# flbmain.net
KiCad netlist of a schematic drawn in Altium Designer
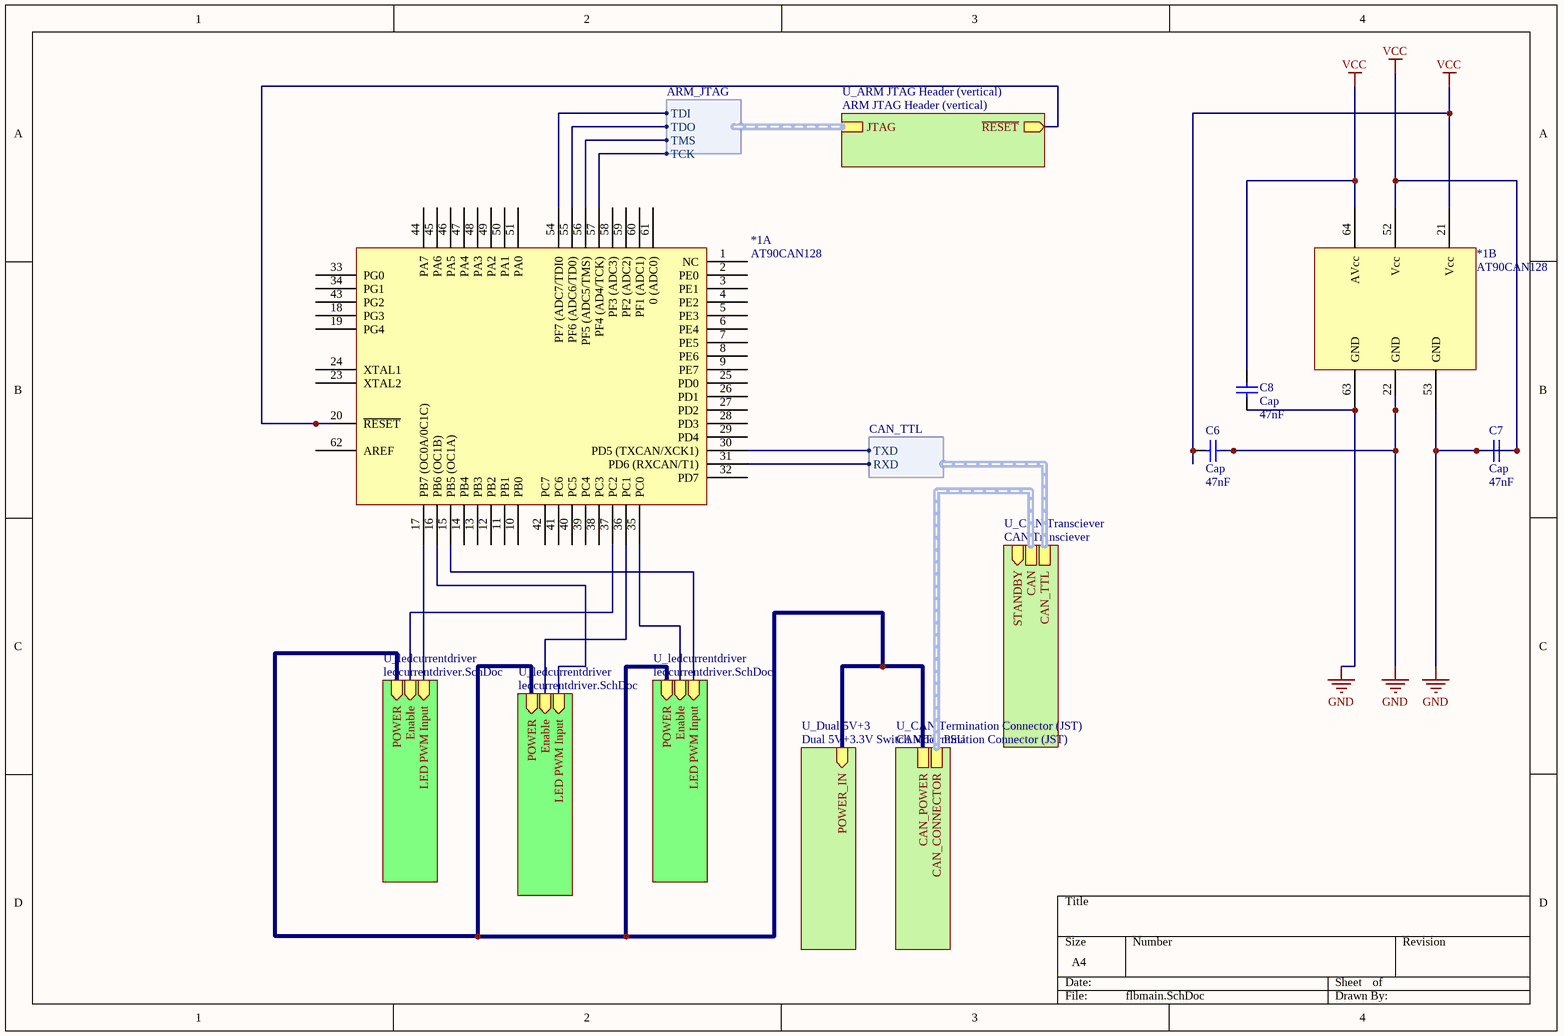
[diagram p0: flbmain.SchDoc]

(export (version "E")
  (design (tool "Eeschema 10.0.6"))
  (components
    (comp (ref "*1")
      (value "AT90CAN128")
      (footprint "TQFP80P1600X1600X120-64N")
      (libsource (lib "") (part "AT90CAN128_1"))
    )
    (comp (ref "C6")
      (value "Cap")
      (footprint "RAD-0.3")
      (description "Capacitor")
      (fields (field (name "ALTIUM_VALUE") "47nF") (field (name "PUBLISHER") "Altium Limited"))
      (libsource (lib "Miscellaneous Devices") (part "Cap"))
    )
    (comp (ref "C7")
      (value "Cap")
      (footprint "RAD-0.3")
      (description "Capacitor")
      (fields (field (name "ALTIUM_VALUE") "47nF") (field (name "PUBLISHER") "Altium Limited"))
      (libsource (lib "Miscellaneous Devices") (part "Cap"))
    )
    (comp (ref "C8")
      (value "Cap")
      (footprint "RAD-0.3")
      (description "Capacitor")
      (fields (field (name "ALTIUM_VALUE") "47nF") (field (name "PUBLISHER") "Altium Limited"))
      (libsource (lib "Miscellaneous Devices") (part "Cap"))
    )
  )
  (nets
    (net (code "5") (name "/Enable") (class "Default")
      (node (ref "*1") (pin "37") (pinfunction "PC2_37") (pintype "passive"))
    )
    (net (code "6") (name "/Enable_1") (class "Default")
      (node (ref "*1") (pin "35") (pinfunction "PC0_35") (pintype "passive"))
    )
    (net (code "7") (name "/Enable_2") (class "Default")
      (node (ref "*1") (pin "36") (pinfunction "PC1_36") (pintype "passive"))
    )
    (net (code "8") (name "/LED PWM Input") (class "Default")
      (node (ref "*1") (pin "17") (pinfunction "PB7_(OC0A/0C1C)_17") (pintype "passive"))
    )
    (net (code "9") (name "/LED PWM Input_1") (class "Default")
      (node (ref "*1") (pin "15") (pinfunction "PB5_(OC1A)_15") (pintype "passive"))
    )
    (net (code "10") (name "/LED PWM Input_2") (class "Default")
      (node (ref "*1") (pin "16") (pinfunction "PB6_(OC1B)_16") (pintype "passive"))
    )
    (net (code "11") (name "/RXD") (class "Default")
      (node (ref "*1") (pin "31") (pinfunction "PD6_(RXCAN/T1)_31") (pintype "passive"))
    )
    (net (code "13") (name "/TCK") (class "Default")
      (node (ref "*1") (pin "57") (pinfunction "PF4_(AD4/TCK)_57") (pintype "passive"))
    )
    (net (code "14") (name "/TDI") (class "Default")
      (node (ref "*1") (pin "54") (pinfunction "PF7_(ADC7/TDI0_54") (pintype "passive"))
    )
    (net (code "15") (name "/TDO") (class "Default")
      (node (ref "*1") (pin "55") (pinfunction "PF6_(ADC6/TD0)_55") (pintype "passive"))
    )
    (net (code "16") (name "/TMS") (class "Default")
      (node (ref "*1") (pin "56") (pinfunction "PF5_(ADC5/TMS)_56") (pintype "passive"))
    )
    (net (code "17") (name "/TXD") (class "Default")
      (node (ref "*1") (pin "30") (pinfunction "PD5_(TXCAN/XCK1)_30") (pintype "passive"))
    )
    (net (code "20") (name "/~{RESET}") (class "Default")
      (node (ref "*1") (pin "20") (pinfunction "~{RESET}_20") (pintype "passive"))
    )
    (net (code "21") (name "GND") (class "Default")
      (node (ref "*1") (pin "21") (pinfunction "Vcc_21") (pintype "passive"))
      (node (ref "*1") (pin "22") (pinfunction "GND_22") (pintype "passive"))
      (node (ref "*1") (pin "52") (pinfunction "Vcc_52") (pintype "passive"))
      (node (ref "*1") (pin "53") (pinfunction "GND_53") (pintype "passive"))
      (node (ref "*1") (pin "63") (pinfunction "GND_63") (pintype "passive"))
      (node (ref "*1") (pin "64") (pinfunction "AVcc_64") (pintype "passive"))
      (node (ref "C6") (pin "1") (pinfunction "1_1") (pintype "passive"))
      (node (ref "C6") (pin "2") (pinfunction "2_2") (pintype "passive"))
      (node (ref "C7") (pin "1") (pinfunction "1_1") (pintype "passive"))
      (node (ref "C7") (pin "2") (pinfunction "2_2") (pintype "passive"))
      (node (ref "C8") (pin "1") (pinfunction "1_1") (pintype "passive"))
      (node (ref "C8") (pin "2") (pinfunction "2_2") (pintype "passive"))
    )
    (net (code "22") (name "unconnected-(*1A-0_(ADC0)-Pad61)") (class "Default")
      (node (ref "*1") (pin "61") (pinfunction "0_(ADC0)_61") (pintype "passive"))
    )
    (net (code "23") (name "unconnected-(*1A-AREF-Pad62)") (class "Default")
      (node (ref "*1") (pin "62") (pinfunction "AREF_62") (pintype "passive"))
    )
    (net (code "24") (name "unconnected-(*1A-NC-Pad1)") (class "Default")
      (node (ref "*1") (pin "1") (pinfunction "NC_1") (pintype "passive"))
    )
    (net (code "25") (name "unconnected-(*1A-PA0-Pad51)") (class "Default")
      (node (ref "*1") (pin "51") (pinfunction "PA0_51") (pintype "passive"))
    )
    (net (code "26") (name "unconnected-(*1A-PA1-Pad50)") (class "Default")
      (node (ref "*1") (pin "50") (pinfunction "PA1_50") (pintype "passive"))
    )
    (net (code "27") (name "unconnected-(*1A-PA2-Pad49)") (class "Default")
      (node (ref "*1") (pin "49") (pinfunction "PA2_49") (pintype "passive"))
    )
    (net (code "28") (name "unconnected-(*1A-PA3-Pad48)") (class "Default")
      (node (ref "*1") (pin "48") (pinfunction "PA3_48") (pintype "passive"))
    )
    (net (code "29") (name "unconnected-(*1A-PA4-Pad47)") (class "Default")
      (node (ref "*1") (pin "47") (pinfunction "PA4_47") (pintype "passive"))
    )
    (net (code "30") (name "unconnected-(*1A-PA5-Pad46)") (class "Default")
      (node (ref "*1") (pin "46") (pinfunction "PA5_46") (pintype "passive"))
    )
    (net (code "31") (name "unconnected-(*1A-PA6-Pad45)") (class "Default")
      (node (ref "*1") (pin "45") (pinfunction "PA6_45") (pintype "passive"))
    )
    (net (code "32") (name "unconnected-(*1A-PA7-Pad44)") (class "Default")
      (node (ref "*1") (pin "44") (pinfunction "PA7_44") (pintype "passive"))
    )
    (net (code "33") (name "unconnected-(*1A-PB0-Pad10)") (class "Default")
      (node (ref "*1") (pin "10") (pinfunction "PB0_10") (pintype "passive"))
    )
    (net (code "34") (name "unconnected-(*1A-PB1-Pad11)") (class "Default")
      (node (ref "*1") (pin "11") (pinfunction "PB1_11") (pintype "passive"))
    )
    (net (code "35") (name "unconnected-(*1A-PB2-Pad12)") (class "Default")
      (node (ref "*1") (pin "12") (pinfunction "PB2_12") (pintype "passive"))
    )
    (net (code "36") (name "unconnected-(*1A-PB3-Pad13)") (class "Default")
      (node (ref "*1") (pin "13") (pinfunction "PB3_13") (pintype "passive"))
    )
    (net (code "37") (name "unconnected-(*1A-PB4-Pad14)") (class "Default")
      (node (ref "*1") (pin "14") (pinfunction "PB4_14") (pintype "passive"))
    )
    (net (code "38") (name "unconnected-(*1A-PC3-Pad38)") (class "Default")
      (node (ref "*1") (pin "38") (pinfunction "PC3_38") (pintype "passive"))
    )
    (net (code "39") (name "unconnected-(*1A-PC4-Pad39)") (class "Default")
      (node (ref "*1") (pin "39") (pinfunction "PC4_39") (pintype "passive"))
    )
    (net (code "40") (name "unconnected-(*1A-PC5-Pad40)") (class "Default")
      (node (ref "*1") (pin "40") (pinfunction "PC5_40") (pintype "passive"))
    )
    (net (code "41") (name "unconnected-(*1A-PC6-Pad41)") (class "Default")
      (node (ref "*1") (pin "41") (pinfunction "PC6_41") (pintype "passive"))
    )
    (net (code "42") (name "unconnected-(*1A-PC7-Pad42)") (class "Default")
      (node (ref "*1") (pin "42") (pinfunction "PC7_42") (pintype "passive"))
    )
    (net (code "43") (name "unconnected-(*1A-PD0-Pad25)") (class "Default")
      (node (ref "*1") (pin "25") (pinfunction "PD0_25") (pintype "passive"))
    )
    (net (code "44") (name "unconnected-(*1A-PD1-Pad26)") (class "Default")
      (node (ref "*1") (pin "26") (pinfunction "PD1_26") (pintype "passive"))
    )
    (net (code "45") (name "unconnected-(*1A-PD2-Pad27)") (class "Default")
      (node (ref "*1") (pin "27") (pinfunction "PD2_27") (pintype "passive"))
    )
    (net (code "46") (name "unconnected-(*1A-PD3-Pad28)") (class "Default")
      (node (ref "*1") (pin "28") (pinfunction "PD3_28") (pintype "passive"))
    )
    (net (code "47") (name "unconnected-(*1A-PD4-Pad29)") (class "Default")
      (node (ref "*1") (pin "29") (pinfunction "PD4_29") (pintype "passive"))
    )
    (net (code "48") (name "unconnected-(*1A-PD7-Pad32)") (class "Default")
      (node (ref "*1") (pin "32") (pinfunction "PD7_32") (pintype "passive"))
    )
    (net (code "49") (name "unconnected-(*1A-PE0-Pad2)") (class "Default")
      (node (ref "*1") (pin "2") (pinfunction "PE0_2") (pintype "passive"))
    )
    (net (code "50") (name "unconnected-(*1A-PE1-Pad3)") (class "Default")
      (node (ref "*1") (pin "3") (pinfunction "PE1_3") (pintype "passive"))
    )
    (net (code "51") (name "unconnected-(*1A-PE2-Pad4)") (class "Default")
      (node (ref "*1") (pin "4") (pinfunction "PE2_4") (pintype "passive"))
    )
    (net (code "52") (name "unconnected-(*1A-PE3-Pad5)") (class "Default")
      (node (ref "*1") (pin "5") (pinfunction "PE3_5") (pintype "passive"))
    )
    (net (code "53") (name "unconnected-(*1A-PE4-Pad6)") (class "Default")
      (node (ref "*1") (pin "6") (pinfunction "PE4_6") (pintype "passive"))
    )
    (net (code "54") (name "unconnected-(*1A-PE5-Pad7)") (class "Default")
      (node (ref "*1") (pin "7") (pinfunction "PE5_7") (pintype "passive"))
    )
    (net (code "55") (name "unconnected-(*1A-PE6-Pad8)") (class "Default")
      (node (ref "*1") (pin "8") (pinfunction "PE6_8") (pintype "passive"))
    )
    (net (code "56") (name "unconnected-(*1A-PE7-Pad9)") (class "Default")
      (node (ref "*1") (pin "9") (pinfunction "PE7_9") (pintype "passive"))
    )
    (net (code "57") (name "unconnected-(*1A-PF1_(ADC1)-Pad60)") (class "Default")
      (node (ref "*1") (pin "60") (pinfunction "PF1_(ADC1)_60") (pintype "passive"))
    )
    (net (code "58") (name "unconnected-(*1A-PF2_(ADC2)-Pad59)") (class "Default")
      (node (ref "*1") (pin "59") (pinfunction "PF2_(ADC2)_59") (pintype "passive"))
    )
    (net (code "59") (name "unconnected-(*1A-PF3_(ADC3)-Pad58)") (class "Default")
      (node (ref "*1") (pin "58") (pinfunction "PF3_(ADC3)_58") (pintype "passive"))
    )
    (net (code "60") (name "unconnected-(*1A-PG0-Pad33)") (class "Default")
      (node (ref "*1") (pin "33") (pinfunction "PG0_33") (pintype "passive"))
    )
    (net (code "61") (name "unconnected-(*1A-PG1-Pad34)") (class "Default")
      (node (ref "*1") (pin "34") (pinfunction "PG1_34") (pintype "passive"))
    )
    (net (code "62") (name "unconnected-(*1A-PG2-Pad43)") (class "Default")
      (node (ref "*1") (pin "43") (pinfunction "PG2_43") (pintype "passive"))
    )
    (net (code "63") (name "unconnected-(*1A-PG3-Pad18)") (class "Default")
      (node (ref "*1") (pin "18") (pinfunction "PG3_18") (pintype "passive"))
    )
    (net (code "64") (name "unconnected-(*1A-PG4-Pad19)") (class "Default")
      (node (ref "*1") (pin "19") (pinfunction "PG4_19") (pintype "passive"))
    )
    (net (code "65") (name "unconnected-(*1A-XTAL1-Pad24)") (class "Default")
      (node (ref "*1") (pin "24") (pinfunction "XTAL1_24") (pintype "passive"))
    )
    (net (code "66") (name "unconnected-(*1A-XTAL2-Pad23)") (class "Default")
      (node (ref "*1") (pin "23") (pinfunction "XTAL2_23") (pintype "passive"))
    )
  )
)
